# topcontroller.net
KiCad netlist of a schematic drawn in Altium Designer
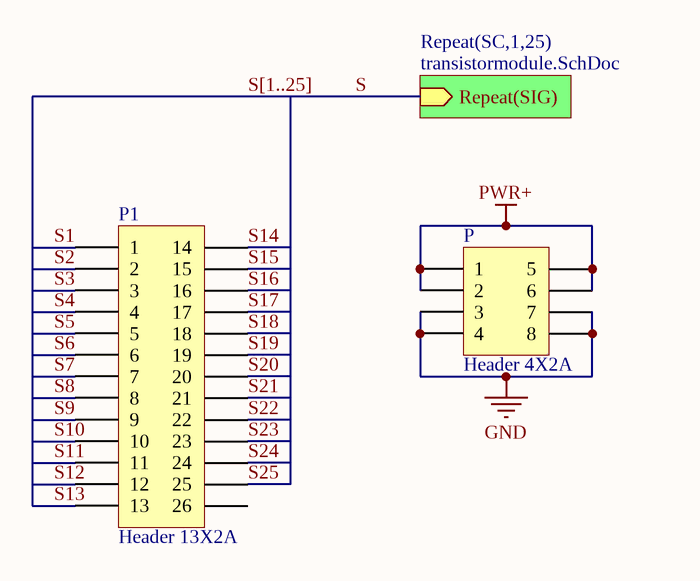
[diagram p0: topcontroller.SchDoc]

(export (version "E")
  (design (tool "Eeschema 10.0.6"))
  (components
    (comp (ref "P")
      (value "Header 4X2A")
      (footprint "HDR2X4_CEN")
      (description "Header, 4-Pin, Dual row")
      (fields (field (name "PUBLISHER") "Altium Limited"))
      (libsource (lib "Miscellaneous Connectors") (part "Header 4X2A"))
    )
    (comp (ref "P1")
      (value "Header 13X2A")
      (footprint "HDR2X13_CEN")
      (description "Header, 13-Pin, Dual row")
      (fields (field (name "PUBLISHER") "Altium Limited"))
      (libsource (lib "Miscellaneous Connectors") (part "Header 13X2A"))
    )
  )
  (nets
    (net (code "2") (name "/S1") (class "Default")
      (node (ref "P1") (pin "1") (pinfunction "1_1") (pintype "passive"))
    )
    (net (code "3") (name "/S2") (class "Default")
      (node (ref "P1") (pin "2") (pinfunction "2_2") (pintype "passive"))
    )
    (net (code "4") (name "/S3") (class "Default")
      (node (ref "P1") (pin "3") (pinfunction "3_3") (pintype "passive"))
    )
    (net (code "5") (name "/S4") (class "Default")
      (node (ref "P1") (pin "4") (pinfunction "4_4") (pintype "passive"))
    )
    (net (code "6") (name "/S5") (class "Default")
      (node (ref "P1") (pin "5") (pinfunction "5_5") (pintype "passive"))
    )
    (net (code "7") (name "/S6") (class "Default")
      (node (ref "P1") (pin "6") (pinfunction "6_6") (pintype "passive"))
    )
    (net (code "8") (name "/S7") (class "Default")
      (node (ref "P1") (pin "7") (pinfunction "7_7") (pintype "passive"))
    )
    (net (code "9") (name "/S8") (class "Default")
      (node (ref "P1") (pin "8") (pinfunction "8_8") (pintype "passive"))
    )
    (net (code "10") (name "/S9") (class "Default")
      (node (ref "P1") (pin "9") (pinfunction "9_9") (pintype "passive"))
    )
    (net (code "11") (name "/S10") (class "Default")
      (node (ref "P1") (pin "10") (pinfunction "10_10") (pintype "passive"))
    )
    (net (code "12") (name "/S11") (class "Default")
      (node (ref "P1") (pin "11") (pinfunction "11_11") (pintype "passive"))
    )
    (net (code "13") (name "/S12") (class "Default")
      (node (ref "P1") (pin "12") (pinfunction "12_12") (pintype "passive"))
    )
    (net (code "14") (name "/S13") (class "Default")
      (node (ref "P1") (pin "13") (pinfunction "13_13") (pintype "passive"))
    )
    (net (code "15") (name "/S14") (class "Default")
      (node (ref "P1") (pin "14") (pinfunction "14_14") (pintype "passive"))
    )
    (net (code "16") (name "/S15") (class "Default")
      (node (ref "P1") (pin "15") (pinfunction "15_15") (pintype "passive"))
    )
    (net (code "17") (name "/S16") (class "Default")
      (node (ref "P1") (pin "16") (pinfunction "16_16") (pintype "passive"))
    )
    (net (code "18") (name "/S17") (class "Default")
      (node (ref "P1") (pin "17") (pinfunction "17_17") (pintype "passive"))
    )
    (net (code "19") (name "/S18") (class "Default")
      (node (ref "P1") (pin "18") (pinfunction "18_18") (pintype "passive"))
    )
    (net (code "20") (name "/S19") (class "Default")
      (node (ref "P1") (pin "19") (pinfunction "19_19") (pintype "passive"))
    )
    (net (code "21") (name "/S20") (class "Default")
      (node (ref "P1") (pin "20") (pinfunction "20_20") (pintype "passive"))
    )
    (net (code "22") (name "/S21") (class "Default")
      (node (ref "P1") (pin "21") (pinfunction "21_21") (pintype "passive"))
    )
    (net (code "23") (name "/S22") (class "Default")
      (node (ref "P1") (pin "22") (pinfunction "22_22") (pintype "passive"))
    )
    (net (code "24") (name "/S23") (class "Default")
      (node (ref "P1") (pin "23") (pinfunction "23_23") (pintype "passive"))
    )
    (net (code "25") (name "/S24") (class "Default")
      (node (ref "P1") (pin "24") (pinfunction "24_24") (pintype "passive"))
    )
    (net (code "26") (name "/S25") (class "Default")
      (node (ref "P1") (pin "25") (pinfunction "25_25") (pintype "passive"))
    )
    (net (code "28") (name "GND") (class "Default")
      (node (ref "P") (pin "3") (pinfunction "3_3") (pintype "passive"))
      (node (ref "P") (pin "4") (pinfunction "4_4") (pintype "passive"))
      (node (ref "P") (pin "7") (pinfunction "7_7") (pintype "passive"))
      (node (ref "P") (pin "8") (pinfunction "8_8") (pintype "passive"))
    )
    (net (code "29") (name "PWR+") (class "Default")
      (node (ref "P") (pin "1") (pinfunction "1_1") (pintype "passive"))
      (node (ref "P") (pin "2") (pinfunction "2_2") (pintype "passive"))
      (node (ref "P") (pin "5") (pinfunction "5_5") (pintype "passive"))
      (node (ref "P") (pin "6") (pinfunction "6_6") (pintype "passive"))
    )
    (net (code "30") (name "unconnected-(P1-Pad26)") (class "Default")
      (node (ref "P1") (pin "26") (pinfunction "26_26") (pintype "passive"))
    )
  )
)
